# LED_ring.net
KiCad netlist of a schematic drawn in Altium Designer
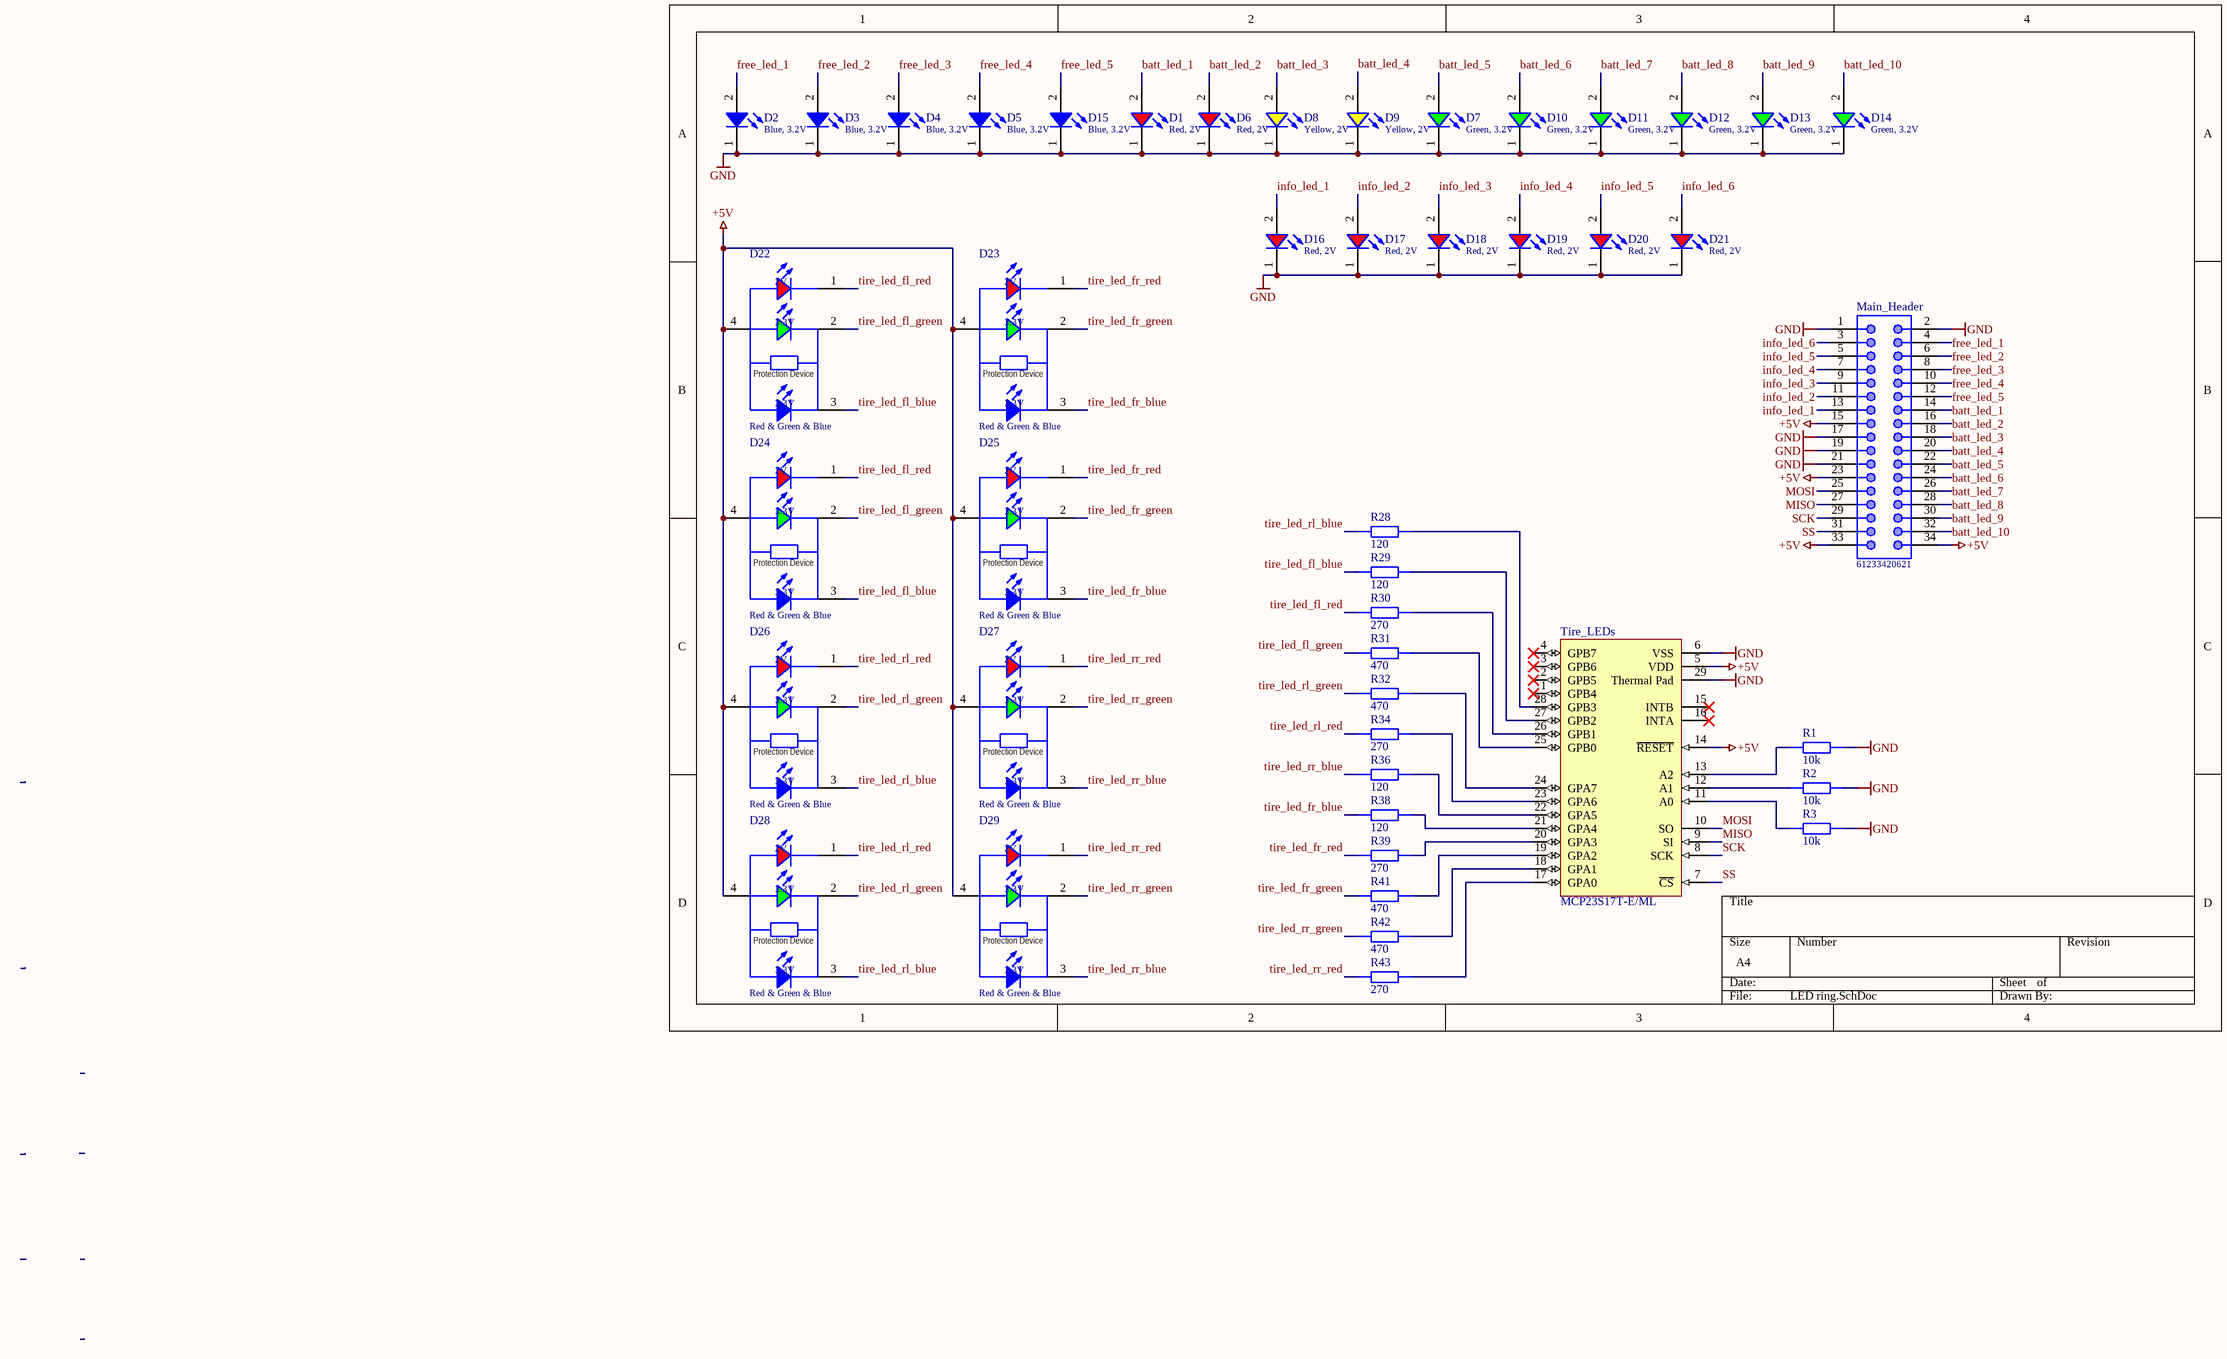
[diagram p0: LED ring.SchDoc]

(export (version "E")
  (design (tool "Eeschema 10.0.6"))
  (components
    (comp (ref "D1")
      (value "Red, 2V")
      (footprint "WL-SMCW_0805")
      (description "WL-SMCW SMT Mono-color Chip LED Waterclear, size 0805, Red, 2V, 140deg")
      (fields (field (name "PART NUMBER") "150080RS75000") (field (name "PUBLISHER") "Wurth Elektronik"))
      (libsource (lib "Altium_WL-SMCW (rev20a)") (part "150080RS75000"))
    )
    (comp (ref "D2")
      (value "Blue, 3.2V")
      (footprint "WL-SMCW_0805")
      (description "WL-SMCW SMT Mono-color Chip LED Waterclear, size 0805, Blue, 3.2V, 140deg")
      (fields (field (name "PART NUMBER") "150080BS75000") (field (name "PUBLISHER") "Wurth Elektronik"))
      (libsource (lib "Altium_WL-SMCW (rev20a)") (part "150080BS75000"))
    )
    (comp (ref "D3")
      (value "Blue, 3.2V")
      (footprint "WL-SMCW_0805")
      (description "WL-SMCW SMT Mono-color Chip LED Waterclear, size 0805, Blue, 3.2V, 140deg")
      (fields (field (name "PART NUMBER") "150080BS75000") (field (name "PUBLISHER") "Wurth Elektronik"))
      (libsource (lib "Altium_WL-SMCW (rev20a)") (part "150080BS75000"))
    )
    (comp (ref "D4")
      (value "Blue, 3.2V")
      (footprint "WL-SMCW_0805")
      (description "WL-SMCW SMT Mono-color Chip LED Waterclear, size 0805, Blue, 3.2V, 140deg")
      (fields (field (name "PART NUMBER") "150080BS75000") (field (name "PUBLISHER") "Wurth Elektronik"))
      (libsource (lib "Altium_WL-SMCW (rev20a)") (part "150080BS75000"))
    )
    (comp (ref "D5")
      (value "Blue, 3.2V")
      (footprint "WL-SMCW_0805")
      (description "WL-SMCW SMT Mono-color Chip LED Waterclear, size 0805, Blue, 3.2V, 140deg")
      (fields (field (name "PART NUMBER") "150080BS75000") (field (name "PUBLISHER") "Wurth Elektronik"))
      (libsource (lib "Altium_WL-SMCW (rev20a)") (part "150080BS75000"))
    )
    (comp (ref "D6")
      (value "Red, 2V")
      (footprint "WL-SMCW_0805")
      (description "WL-SMCW SMT Mono-color Chip LED Waterclear, size 0805, Red, 2V, 140deg")
      (fields (field (name "PART NUMBER") "150080RS75000") (field (name "PUBLISHER") "Wurth Elektronik"))
      (libsource (lib "Altium_WL-SMCW (rev20a)") (part "150080RS75000"))
    )
    (comp (ref "D7")
      (value "Green, 3.2V")
      (footprint "WL-SMCW_0805")
      (description "WL-SMCW SMT Mono-color Chip LED Waterclear, size 0805, Green, 3.2V, 140deg")
      (fields (field (name "PART NUMBER") "150080GS75000") (field (name "PUBLISHER") "Wurth Elektronik"))
      (libsource (lib "Altium_WL-SMCW (rev20a)") (part "150080GS75000"))
    )
    (comp (ref "D8")
      (value "Yellow, 2V")
      (footprint "WL-SMCW_0805")
      (description "WL-SMCW SMT Mono-color Chip LED Waterclear, size 0805, Yellow, 2V, 140deg")
      (fields (field (name "PART NUMBER") "150080YS75000") (field (name "PUBLISHER") "Wurth Elektronik"))
      (libsource (lib "Altium_WL-SMCW (rev20a)") (part "150080YS75000"))
    )
    (comp (ref "D9")
      (value "Yellow, 2V")
      (footprint "WL-SMCW_0805")
      (description "WL-SMCW SMT Mono-color Chip LED Waterclear, size 0805, Yellow, 2V, 140deg")
      (fields (field (name "PART NUMBER") "150080YS75000") (field (name "PUBLISHER") "Wurth Elektronik"))
      (libsource (lib "Altium_WL-SMCW (rev20a)") (part "150080YS75000"))
    )
    (comp (ref "D10")
      (value "Green, 3.2V")
      (footprint "WL-SMCW_0805")
      (description "WL-SMCW SMT Mono-color Chip LED Waterclear, size 0805, Green, 3.2V, 140deg")
      (fields (field (name "PART NUMBER") "150080GS75000") (field (name "PUBLISHER") "Wurth Elektronik"))
      (libsource (lib "Altium_WL-SMCW (rev20a)") (part "150080GS75000"))
    )
    (comp (ref "D11")
      (value "Green, 3.2V")
      (footprint "WL-SMCW_0805")
      (description "WL-SMCW SMT Mono-color Chip LED Waterclear, size 0805, Green, 3.2V, 140deg")
      (fields (field (name "PART NUMBER") "150080GS75000") (field (name "PUBLISHER") "Wurth Elektronik"))
      (libsource (lib "Altium_WL-SMCW (rev20a)") (part "150080GS75000"))
    )
    (comp (ref "D12")
      (value "Green, 3.2V")
      (footprint "WL-SMCW_0805")
      (description "WL-SMCW SMT Mono-color Chip LED Waterclear, size 0805, Green, 3.2V, 140deg")
      (fields (field (name "PART NUMBER") "150080GS75000") (field (name "PUBLISHER") "Wurth Elektronik"))
      (libsource (lib "Altium_WL-SMCW (rev20a)") (part "150080GS75000"))
    )
    (comp (ref "D13")
      (value "Green, 3.2V")
      (footprint "WL-SMCW_0805")
      (description "WL-SMCW SMT Mono-color Chip LED Waterclear, size 0805, Green, 3.2V, 140deg")
      (fields (field (name "PART NUMBER") "150080GS75000") (field (name "PUBLISHER") "Wurth Elektronik"))
      (libsource (lib "Altium_WL-SMCW (rev20a)") (part "150080GS75000"))
    )
    (comp (ref "D14")
      (value "Green, 3.2V")
      (footprint "WL-SMCW_0805")
      (description "WL-SMCW SMT Mono-color Chip LED Waterclear, size 0805, Green, 3.2V, 140deg")
      (fields (field (name "PART NUMBER") "150080GS75000") (field (name "PUBLISHER") "Wurth Elektronik"))
      (libsource (lib "Altium_WL-SMCW (rev20a)") (part "150080GS75000"))
    )
    (comp (ref "D15")
      (value "Blue, 3.2V")
      (footprint "WL-SMCW_0805")
      (description "WL-SMCW SMT Mono-color Chip LED Waterclear, size 0805, Blue, 3.2V, 140deg")
      (fields (field (name "PART NUMBER") "150080BS75000") (field (name "PUBLISHER") "Wurth Elektronik"))
      (libsource (lib "Altium_WL-SMCW (rev20a)") (part "150080BS75000"))
    )
    (comp (ref "D16")
      (value "Red, 2V")
      (footprint "WL-SMCW_0805")
      (description "WL-SMCW SMT Mono-color Chip LED Waterclear, size 0805, Red, 2V, 140deg")
      (fields (field (name "PART NUMBER") "150080RS75000") (field (name "PUBLISHER") "Wurth Elektronik"))
      (libsource (lib "Altium_WL-SMCW (rev20a)") (part "150080RS75000"))
    )
    (comp (ref "D17")
      (value "Red, 2V")
      (footprint "WL-SMCW_0805")
      (description "WL-SMCW SMT Mono-color Chip LED Waterclear, size 0805, Red, 2V, 140deg")
      (fields (field (name "PART NUMBER") "150080RS75000") (field (name "PUBLISHER") "Wurth Elektronik"))
      (libsource (lib "Altium_WL-SMCW (rev20a)") (part "150080RS75000"))
    )
    (comp (ref "D18")
      (value "Red, 2V")
      (footprint "WL-SMCW_0805")
      (description "WL-SMCW SMT Mono-color Chip LED Waterclear, size 0805, Red, 2V, 140deg")
      (fields (field (name "PART NUMBER") "150080RS75000") (field (name "PUBLISHER") "Wurth Elektronik"))
      (libsource (lib "Altium_WL-SMCW (rev20a)") (part "150080RS75000"))
    )
    (comp (ref "D19")
      (value "Red, 2V")
      (footprint "WL-SMCW_0805")
      (description "WL-SMCW SMT Mono-color Chip LED Waterclear, size 0805, Red, 2V, 140deg")
      (fields (field (name "PART NUMBER") "150080RS75000") (field (name "PUBLISHER") "Wurth Elektronik"))
      (libsource (lib "Altium_WL-SMCW (rev20a)") (part "150080RS75000"))
    )
    (comp (ref "D20")
      (value "Red, 2V")
      (footprint "WL-SMCW_0805")
      (description "WL-SMCW SMT Mono-color Chip LED Waterclear, size 0805, Red, 2V, 140deg")
      (fields (field (name "PART NUMBER") "150080RS75000") (field (name "PUBLISHER") "Wurth Elektronik"))
      (libsource (lib "Altium_WL-SMCW (rev20a)") (part "150080RS75000"))
    )
    (comp (ref "D21")
      (value "Red, 2V")
      (footprint "WL-SMCW_0805")
      (description "WL-SMCW SMT Mono-color Chip LED Waterclear, size 0805, Red, 2V, 140deg")
      (fields (field (name "PART NUMBER") "150080RS75000") (field (name "PUBLISHER") "Wurth Elektronik"))
      (libsource (lib "Altium_WL-SMCW (rev20a)") (part "150080RS75000"))
    )
    (comp (ref "D22")
      (value "Red & Green & Blue")
      (footprint "WL-SFCW_0805")
      (description "WL-SFCW SMT Full-color Chip LED Waterclear, size 0805, Red & Green & Blue, 120deg")
      (fields (field (name "PART NUMBER") "150080M173000") (field (name "PUBLISHER") "Wurth Elektronik"))
      (libsource (lib "Altium_WL-SFCW (rev19b)") (part "150080M173000"))
    )
    (comp (ref "D23")
      (value "Red & Green & Blue")
      (footprint "WL-SFCW_0805")
      (description "WL-SFCW SMT Full-color Chip LED Waterclear, size 0805, Red & Green & Blue, 120deg")
      (fields (field (name "PART NUMBER") "150080M173000") (field (name "PUBLISHER") "Wurth Elektronik"))
      (libsource (lib "Altium_WL-SFCW (rev19b)") (part "150080M173000"))
    )
    (comp (ref "D24")
      (value "Red & Green & Blue")
      (footprint "WL-SFCW_0805")
      (description "WL-SFCW SMT Full-color Chip LED Waterclear, size 0805, Red & Green & Blue, 120deg")
      (fields (field (name "PART NUMBER") "150080M173000") (field (name "PUBLISHER") "Wurth Elektronik"))
      (libsource (lib "Altium_WL-SFCW (rev19b)") (part "150080M173000"))
    )
    (comp (ref "D25")
      (value "Red & Green & Blue")
      (footprint "WL-SFCW_0805")
      (description "WL-SFCW SMT Full-color Chip LED Waterclear, size 0805, Red & Green & Blue, 120deg")
      (fields (field (name "PART NUMBER") "150080M173000") (field (name "PUBLISHER") "Wurth Elektronik"))
      (libsource (lib "Altium_WL-SFCW (rev19b)") (part "150080M173000"))
    )
    (comp (ref "D26")
      (value "Red & Green & Blue")
      (footprint "WL-SFCW_0805")
      (description "WL-SFCW SMT Full-color Chip LED Waterclear, size 0805, Red & Green & Blue, 120deg")
      (fields (field (name "PART NUMBER") "150080M173000") (field (name "PUBLISHER") "Wurth Elektronik"))
      (libsource (lib "Altium_WL-SFCW (rev19b)") (part "150080M173000"))
    )
    (comp (ref "D27")
      (value "Red & Green & Blue")
      (footprint "WL-SFCW_0805")
      (description "WL-SFCW SMT Full-color Chip LED Waterclear, size 0805, Red & Green & Blue, 120deg")
      (fields (field (name "PART NUMBER") "150080M173000") (field (name "PUBLISHER") "Wurth Elektronik"))
      (libsource (lib "Altium_WL-SFCW (rev19b)") (part "150080M173000"))
    )
    (comp (ref "D28")
      (value "Red & Green & Blue")
      (footprint "WL-SFCW_0805")
      (description "WL-SFCW SMT Full-color Chip LED Waterclear, size 0805, Red & Green & Blue, 120deg")
      (fields (field (name "PART NUMBER") "150080M173000") (field (name "PUBLISHER") "Wurth Elektronik"))
      (libsource (lib "Altium_WL-SFCW (rev19b)") (part "150080M173000"))
    )
    (comp (ref "D29")
      (value "Red & Green & Blue")
      (footprint "WL-SFCW_0805")
      (description "WL-SFCW SMT Full-color Chip LED Waterclear, size 0805, Red & Green & Blue, 120deg")
      (fields (field (name "PART NUMBER") "150080M173000") (field (name "PUBLISHER") "Wurth Elektronik"))
      (libsource (lib "Altium_WL-SFCW (rev19b)") (part "150080M173000"))
    )
    (comp (ref "Main_Header")
      (value "61233420621")
      (footprint "61233420621")
      (description "WR-BHD Box Header, Male PCB side, pitch 2.54mm, SMT, Straight, 34p")
      (fields (field (name "MANUFACTURER") "Wurth Elektronik"))
      (libsource (lib "Altium_WR-BHD (rev21a)") (part "61233420621"))
    )
    (comp (ref "R1")
      (value "10k")
      (footprint "STACKPOLE CSR0603")
      (description "Resistor with multiple footprints")
      (fields (field (name "Comment") "SMD Resistor"))
      (libsource (lib "Standardbauteile") (part "SMD Resistor"))
    )
    (comp (ref "R2")
      (value "10k")
      (footprint "STACKPOLE CSR0603")
      (description "Resistor with multiple footprints")
      (fields (field (name "Comment") "SMD Resistor"))
      (libsource (lib "Standardbauteile") (part "SMD Resistor"))
    )
    (comp (ref "R3")
      (value "10k")
      (footprint "STACKPOLE CSR0603")
      (description "Resistor with multiple footprints")
      (fields (field (name "Comment") "SMD Resistor"))
      (libsource (lib "Standardbauteile") (part "SMD Resistor"))
    )
    (comp (ref "R28")
      (value "120")
      (footprint "STACKPOLE CSR0603")
      (description "Resistor with multiple footprints")
      (fields (field (name "Comment") "SMD Resistor"))
      (libsource (lib "Standardbauteile") (part "SMD Resistor"))
    )
    (comp (ref "R29")
      (value "120")
      (footprint "STACKPOLE CSR0603")
      (description "Resistor with multiple footprints")
      (fields (field (name "Comment") "SMD Resistor"))
      (libsource (lib "Standardbauteile") (part "SMD Resistor"))
    )
    (comp (ref "R30")
      (value "270")
      (footprint "STACKPOLE CSR0603")
      (description "Resistor with multiple footprints")
      (fields (field (name "Comment") "SMD Resistor"))
      (libsource (lib "Standardbauteile") (part "SMD Resistor"))
    )
    (comp (ref "R31")
      (value "470")
      (footprint "STACKPOLE CSR0603")
      (description "Resistor with multiple footprints")
      (fields (field (name "Comment") "SMD Resistor"))
      (libsource (lib "Standardbauteile") (part "SMD Resistor"))
    )
    (comp (ref "R32")
      (value "470")
      (footprint "STACKPOLE CSR0603")
      (description "Resistor with multiple footprints")
      (fields (field (name "Comment") "SMD Resistor"))
      (libsource (lib "Standardbauteile") (part "SMD Resistor"))
    )
    (comp (ref "R34")
      (value "270")
      (footprint "STACKPOLE CSR0603")
      (description "Resistor with multiple footprints")
      (fields (field (name "Comment") "SMD Resistor"))
      (libsource (lib "Standardbauteile") (part "SMD Resistor"))
    )
    (comp (ref "R36")
      (value "120")
      (footprint "STACKPOLE CSR0603")
      (description "Resistor with multiple footprints")
      (fields (field (name "Comment") "SMD Resistor"))
      (libsource (lib "Standardbauteile") (part "SMD Resistor"))
    )
    (comp (ref "R38")
      (value "120")
      (footprint "STACKPOLE CSR0603")
      (description "Resistor with multiple footprints")
      (fields (field (name "Comment") "SMD Resistor"))
      (libsource (lib "Standardbauteile") (part "SMD Resistor"))
    )
    (comp (ref "R39")
      (value "270")
      (footprint "STACKPOLE CSR0603")
      (description "Resistor with multiple footprints")
      (fields (field (name "Comment") "SMD Resistor"))
      (libsource (lib "Standardbauteile") (part "SMD Resistor"))
    )
    (comp (ref "R41")
      (value "470")
      (footprint "STACKPOLE CSR0603")
      (description "Resistor with multiple footprints")
      (fields (field (name "Comment") "SMD Resistor"))
      (libsource (lib "Standardbauteile") (part "SMD Resistor"))
    )
    (comp (ref "R42")
      (value "470")
      (footprint "STACKPOLE CSR0603")
      (description "Resistor with multiple footprints")
      (fields (field (name "Comment") "SMD Resistor"))
      (libsource (lib "Standardbauteile") (part "SMD Resistor"))
    )
    (comp (ref "R43")
      (value "270")
      (footprint "STACKPOLE CSR0603")
      (description "Resistor with multiple footprints")
      (fields (field (name "Comment") "SMD Resistor"))
      (libsource (lib "Standardbauteile") (part "SMD Resistor"))
    )
    (comp (ref "Tire_LEDs")
      (value "MCP23S17T-E/ML")
      (footprint "QFN-ML28_M")
      (description "16-Bit I/O Expander with Serial Interface, 28-Pin QFN, Extended Temperature, Tape and Reel")
      (libsource (lib "Altium Content Vault") (part "PR-BUSIC-MCP23S17-29"))
    )
  )
  (nets
    (net (code "1") (name "+5V") (class "Default")
      (node (ref "D22") (pin "4") (pinfunction "A_4") (pintype "passive"))
      (node (ref "D23") (pin "4") (pinfunction "A_4") (pintype "passive"))
      (node (ref "D24") (pin "4") (pinfunction "A_4") (pintype "passive"))
      (node (ref "D25") (pin "4") (pinfunction "A_4") (pintype "passive"))
      (node (ref "D26") (pin "4") (pinfunction "A_4") (pintype "passive"))
      (node (ref "D27") (pin "4") (pinfunction "A_4") (pintype "passive"))
      (node (ref "D28") (pin "4") (pinfunction "A_4") (pintype "passive"))
      (node (ref "D29") (pin "4") (pinfunction "A_4") (pintype "passive"))
      (node (ref "Main_Header") (pin "15") (pinfunction "15_15") (pintype "passive"))
      (node (ref "Main_Header") (pin "23") (pinfunction "23_23") (pintype "passive"))
      (node (ref "Main_Header") (pin "33") (pinfunction "33_33") (pintype "passive"))
      (node (ref "Main_Header") (pin "34") (pinfunction "34_34") (pintype "passive"))
      (node (ref "Tire_LEDs") (pin "14") (pinfunction "~{RESET}_14") (pintype "input"))
      (node (ref "Tire_LEDs") (pin "5") (pinfunction "VDD_5") (pintype "power_in"))
    )
    (net (code "2") (name "/MISO") (class "Default")
      (node (ref "Main_Header") (pin "27") (pinfunction "27_27") (pintype "passive"))
      (node (ref "Tire_LEDs") (pin "9") (pinfunction "SI_9") (pintype "input"))
    )
    (net (code "3") (name "/MOSI") (class "Default")
      (node (ref "Main_Header") (pin "25") (pinfunction "25_25") (pintype "passive"))
      (node (ref "Tire_LEDs") (pin "10") (pinfunction "SO_10") (pintype "tri_state"))
    )
    (net (code "4") (name "/SCK") (class "Default")
      (node (ref "Main_Header") (pin "29") (pinfunction "29_29") (pintype "passive"))
      (node (ref "Tire_LEDs") (pin "8") (pinfunction "SCK_8") (pintype "input"))
    )
    (net (code "5") (name "/SS") (class "Default")
      (node (ref "Main_Header") (pin "31") (pinfunction "31_31") (pintype "passive"))
      (node (ref "Tire_LEDs") (pin "7") (pinfunction "~{CS}_7") (pintype "input"))
    )
    (net (code "6") (name "/batt_led_1") (class "Default")
      (node (ref "D1") (pin "2") (pinfunction "A_2") (pintype "passive"))
      (node (ref "Main_Header") (pin "14") (pinfunction "14_14") (pintype "passive"))
    )
    (net (code "7") (name "/batt_led_2") (class "Default")
      (node (ref "D6") (pin "2") (pinfunction "A_2") (pintype "passive"))
      (node (ref "Main_Header") (pin "16") (pinfunction "16_16") (pintype "passive"))
    )
    (net (code "8") (name "/batt_led_3") (class "Default")
      (node (ref "D8") (pin "2") (pinfunction "A_2") (pintype "passive"))
      (node (ref "Main_Header") (pin "18") (pinfunction "18_18") (pintype "passive"))
    )
    (net (code "9") (name "/batt_led_4") (class "Default")
      (node (ref "D9") (pin "2") (pinfunction "A_2") (pintype "passive"))
      (node (ref "Main_Header") (pin "20") (pinfunction "20_20") (pintype "passive"))
    )
    (net (code "10") (name "/batt_led_5") (class "Default")
      (node (ref "D7") (pin "2") (pinfunction "A_2") (pintype "passive"))
      (node (ref "Main_Header") (pin "22") (pinfunction "22_22") (pintype "passive"))
    )
    (net (code "11") (name "/batt_led_6") (class "Default")
      (node (ref "D10") (pin "2") (pinfunction "A_2") (pintype "passive"))
      (node (ref "Main_Header") (pin "24") (pinfunction "24_24") (pintype "passive"))
    )
    (net (code "12") (name "/batt_led_7") (class "Default")
      (node (ref "D11") (pin "2") (pinfunction "A_2") (pintype "passive"))
      (node (ref "Main_Header") (pin "26") (pinfunction "26_26") (pintype "passive"))
    )
    (net (code "13") (name "/batt_led_8") (class "Default")
      (node (ref "D12") (pin "2") (pinfunction "A_2") (pintype "passive"))
      (node (ref "Main_Header") (pin "28") (pinfunction "28_28") (pintype "passive"))
    )
    (net (code "14") (name "/batt_led_9") (class "Default")
      (node (ref "D13") (pin "2") (pinfunction "A_2") (pintype "passive"))
      (node (ref "Main_Header") (pin "30") (pinfunction "30_30") (pintype "passive"))
    )
    (net (code "15") (name "/batt_led_10") (class "Default")
      (node (ref "D14") (pin "2") (pinfunction "A_2") (pintype "passive"))
      (node (ref "Main_Header") (pin "32") (pinfunction "32_32") (pintype "passive"))
    )
    (net (code "16") (name "/free_led_1") (class "Default")
      (node (ref "D2") (pin "2") (pinfunction "A_2") (pintype "passive"))
      (node (ref "Main_Header") (pin "4") (pinfunction "4_4") (pintype "passive"))
    )
    (net (code "17") (name "/free_led_2") (class "Default")
      (node (ref "D3") (pin "2") (pinfunction "A_2") (pintype "passive"))
      (node (ref "Main_Header") (pin "6") (pinfunction "6_6") (pintype "passive"))
    )
    (net (code "18") (name "/free_led_3") (class "Default")
      (node (ref "D4") (pin "2") (pinfunction "A_2") (pintype "passive"))
      (node (ref "Main_Header") (pin "8") (pinfunction "8_8") (pintype "passive"))
    )
    (net (code "19") (name "/free_led_4") (class "Default")
      (node (ref "D5") (pin "2") (pinfunction "A_2") (pintype "passive"))
      (node (ref "Main_Header") (pin "10") (pinfunction "10_10") (pintype "passive"))
    )
    (net (code "20") (name "/free_led_5") (class "Default")
      (node (ref "D15") (pin "2") (pinfunction "A_2") (pintype "passive"))
      (node (ref "Main_Header") (pin "12") (pinfunction "12_12") (pintype "passive"))
    )
    (net (code "21") (name "/info_led_1") (class "Default")
      (node (ref "D16") (pin "2") (pinfunction "A_2") (pintype "passive"))
      (node (ref "Main_Header") (pin "13") (pinfunction "13_13") (pintype "passive"))
    )
    (net (code "22") (name "/info_led_2") (class "Default")
      (node (ref "D17") (pin "2") (pinfunction "A_2") (pintype "passive"))
      (node (ref "Main_Header") (pin "11") (pinfunction "11_11") (pintype "passive"))
    )
    (net (code "23") (name "/info_led_3") (class "Default")
      (node (ref "D18") (pin "2") (pinfunction "A_2") (pintype "passive"))
      (node (ref "Main_Header") (pin "9") (pinfunction "9_9") (pintype "passive"))
    )
    (net (code "24") (name "/info_led_4") (class "Default")
      (node (ref "D19") (pin "2") (pinfunction "A_2") (pintype "passive"))
      (node (ref "Main_Header") (pin "7") (pinfunction "7_7") (pintype "passive"))
    )
    (net (code "25") (name "/info_led_5") (class "Default")
      (node (ref "D20") (pin "2") (pinfunction "A_2") (pintype "passive"))
      (node (ref "Main_Header") (pin "5") (pinfunction "5_5") (pintype "passive"))
    )
    (net (code "26") (name "/info_led_6") (class "Default")
      (node (ref "D21") (pin "2") (pinfunction "A_2") (pintype "passive"))
      (node (ref "Main_Header") (pin "3") (pinfunction "3_3") (pintype "passive"))
    )
    (net (code "27") (name "/tire_led_fl_blue") (class "Default")
      (node (ref "D22") (pin "3") (pinfunction "K_3") (pintype "passive"))
      (node (ref "D24") (pin "3") (pinfunction "K_3") (pintype "passive"))
      (node (ref "R29") (pin "2") (pinfunction "2_2") (pintype "passive"))
    )
    (net (code "28") (name "/tire_led_fl_green") (class "Default")
      (node (ref "D22") (pin "2") (pinfunction "K_2") (pintype "passive"))
      (node (ref "D24") (pin "2") (pinfunction "K_2") (pintype "passive"))
      (node (ref "R31") (pin "2") (pinfunction "2_2") (pintype "passive"))
    )
    (net (code "29") (name "/tire_led_fl_red") (class "Default")
      (node (ref "D22") (pin "1") (pinfunction "K_1") (pintype "passive"))
      (node (ref "D24") (pin "1") (pinfunction "K_1") (pintype "passive"))
      (node (ref "R30") (pin "2") (pinfunction "2_2") (pintype "passive"))
    )
    (net (code "30") (name "/tire_led_fr_blue") (class "Default")
      (node (ref "D23") (pin "3") (pinfunction "K_3") (pintype "passive"))
      (node (ref "D25") (pin "3") (pinfunction "K_3") (pintype "passive"))
      (node (ref "R38") (pin "2") (pinfunction "2_2") (pintype "passive"))
    )
    (net (code "31") (name "/tire_led_fr_green") (class "Default")
      (node (ref "D23") (pin "2") (pinfunction "K_2") (pintype "passive"))
      (node (ref "D25") (pin "2") (pinfunction "K_2") (pintype "passive"))
      (node (ref "R41") (pin "2") (pinfunction "2_2") (pintype "passive"))
    )
    (net (code "32") (name "/tire_led_fr_red") (class "Default")
      (node (ref "D23") (pin "1") (pinfunction "K_1") (pintype "passive"))
      (node (ref "D25") (pin "1") (pinfunction "K_1") (pintype "passive"))
      (node (ref "R39") (pin "2") (pinfunction "2_2") (pintype "passive"))
    )
    (net (code "33") (name "/tire_led_rl_blue") (class "Default")
      (node (ref "D26") (pin "3") (pinfunction "K_3") (pintype "passive"))
      (node (ref "D28") (pin "3") (pinfunction "K_3") (pintype "passive"))
      (node (ref "R28") (pin "2") (pinfunction "2_2") (pintype "passive"))
    )
    (net (code "34") (name "/tire_led_rl_green") (class "Default")
      (node (ref "D26") (pin "2") (pinfunction "K_2") (pintype "passive"))
      (node (ref "D28") (pin "2") (pinfunction "K_2") (pintype "passive"))
      (node (ref "R32") (pin "2") (pinfunction "2_2") (pintype "passive"))
    )
    (net (code "35") (name "/tire_led_rl_red") (class "Default")
      (node (ref "D26") (pin "1") (pinfunction "K_1") (pintype "passive"))
      (node (ref "D28") (pin "1") (pinfunction "K_1") (pintype "passive"))
      (node (ref "R34") (pin "2") (pinfunction "2_2") (pintype "passive"))
    )
    (net (code "36") (name "/tire_led_rr_blue") (class "Default")
      (node (ref "D27") (pin "3") (pinfunction "K_3") (pintype "passive"))
      (node (ref "D29") (pin "3") (pinfunction "K_3") (pintype "passive"))
      (node (ref "R36") (pin "2") (pinfunction "2_2") (pintype "passive"))
    )
    (net (code "37") (name "/tire_led_rr_green") (class "Default")
      (node (ref "D27") (pin "2") (pinfunction "K_2") (pintype "passive"))
      (node (ref "D29") (pin "2") (pinfunction "K_2") (pintype "passive"))
      (node (ref "R42") (pin "2") (pinfunction "2_2") (pintype "passive"))
    )
    (net (code "38") (name "/tire_led_rr_red") (class "Default")
      (node (ref "D27") (pin "1") (pinfunction "K_1") (pintype "passive"))
      (node (ref "D29") (pin "1") (pinfunction "K_1") (pintype "passive"))
      (node (ref "R43") (pin "2") (pinfunction "2_2") (pintype "passive"))
    )
    (net (code "39") (name "GND") (class "Default")
      (node (ref "D1") (pin "1") (pinfunction "K_1") (pintype "passive"))
      (node (ref "D10") (pin "1") (pinfunction "K_1") (pintype "passive"))
      (node (ref "D11") (pin "1") (pinfunction "K_1") (pintype "passive"))
      (node (ref "D12") (pin "1") (pinfunction "K_1") (pintype "passive"))
      (node (ref "D13") (pin "1") (pinfunction "K_1") (pintype "passive"))
      (node (ref "D14") (pin "1") (pinfunction "K_1") (pintype "passive"))
      (node (ref "D15") (pin "1") (pinfunction "K_1") (pintype "passive"))
      (node (ref "D16") (pin "1") (pinfunction "K_1") (pintype "passive"))
      (node (ref "D17") (pin "1") (pinfunction "K_1") (pintype "passive"))
      (node (ref "D18") (pin "1") (pinfunction "K_1") (pintype "passive"))
      (node (ref "D19") (pin "1") (pinfunction "K_1") (pintype "passive"))
      (node (ref "D2") (pin "1") (pinfunction "K_1") (pintype "passive"))
      (node (ref "D20") (pin "1") (pinfunction "K_1") (pintype "passive"))
      (node (ref "D21") (pin "1") (pinfunction "K_1") (pintype "passive"))
      (node (ref "D3") (pin "1") (pinfunction "K_1") (pintype "passive"))
      (node (ref "D4") (pin "1") (pinfunction "K_1") (pintype "passive"))
      (node (ref "D5") (pin "1") (pinfunction "K_1") (pintype "passive"))
      (node (ref "D6") (pin "1") (pinfunction "K_1") (pintype "passive"))
      (node (ref "D7") (pin "1") (pinfunction "K_1") (pintype "passive"))
      (node (ref "D8") (pin "1") (pinfunction "K_1") (pintype "passive"))
      (node (ref "D9") (pin "1") (pinfunction "K_1") (pintype "passive"))
      (node (ref "Main_Header") (pin "1") (pinfunction "1_1") (pintype "passive"))
      (node (ref "Main_Header") (pin "17") (pinfunction "17_17") (pintype "passive"))
      (node (ref "Main_Header") (pin "19") (pinfunction "19_19") (pintype "passive"))
      (node (ref "Main_Header") (pin "2") (pinfunction "2_2") (pintype "passive"))
      (node (ref "Main_Header") (pin "21") (pinfunction "21_21") (pintype "passive"))
      (node (ref "R1") (pin "2") (pinfunction "2_2") (pintype "passive"))
      (node (ref "R2") (pin "2") (pinfunction "2_2") (pintype "passive"))
      (node (ref "R3") (pin "2") (pinfunction "2_2") (pintype "passive"))
      (node (ref "Tire_LEDs") (pin "29") (pinfunction "Thermal_Pad_29") (pintype "passive"))
      (node (ref "Tire_LEDs") (pin "6") (pinfunction "VSS_6") (pintype "power_in"))
    )
    (net (code "40") (name "Net-(Tire_LEDs-A0)") (class "Default")
      (node (ref "R3") (pin "1") (pinfunction "1_1") (pintype "passive"))
      (node (ref "Tire_LEDs") (pin "11") (pinfunction "A0_11") (pintype "input"))
    )
    (net (code "41") (name "Net-(Tire_LEDs-A1)") (class "Default")
      (node (ref "R2") (pin "1") (pinfunction "1_1") (pintype "passive"))
      (node (ref "Tire_LEDs") (pin "12") (pinfunction "A1_12") (pintype "input"))
    )
    (net (code "42") (name "Net-(Tire_LEDs-A2)") (class "Default")
      (node (ref "R1") (pin "1") (pinfunction "1_1") (pintype "passive"))
      (node (ref "Tire_LEDs") (pin "13") (pinfunction "A2_13") (pintype "input"))
    )
    (net (code "43") (name "Net-(Tire_LEDs-GPA0)") (class "Default")
      (node (ref "R43") (pin "1") (pinfunction "1_1") (pintype "passive"))
      (node (ref "Tire_LEDs") (pin "17") (pinfunction "GPA0_17") (pintype "bidirectional"))
    )
    (net (code "44") (name "Net-(Tire_LEDs-GPA1)") (class "Default")
      (node (ref "R42") (pin "1") (pinfunction "1_1") (pintype "passive"))
      (node (ref "Tire_LEDs") (pin "18") (pinfunction "GPA1_18") (pintype "bidirectional"))
    )
    (net (code "45") (name "Net-(Tire_LEDs-GPA2)") (class "Default")
      (node (ref "R41") (pin "1") (pinfunction "1_1") (pintype "passive"))
      (node (ref "Tire_LEDs") (pin "19") (pinfunction "GPA2_19") (pintype "bidirectional"))
    )
    (net (code "46") (name "Net-(Tire_LEDs-GPA3)") (class "Default")
      (node (ref "R39") (pin "1") (pinfunction "1_1") (pintype "passive"))
      (node (ref "Tire_LEDs") (pin "20") (pinfunction "GPA3_20") (pintype "bidirectional"))
    )
    (net (code "47") (name "Net-(Tire_LEDs-GPA4)") (class "Default")
      (node (ref "R38") (pin "1") (pinfunction "1_1") (pintype "passive"))
      (node (ref "Tire_LEDs") (pin "21") (pinfunction "GPA4_21") (pintype "bidirectional"))
    )
    (net (code "48") (name "Net-(Tire_LEDs-GPA5)") (class "Default")
      (node (ref "R36") (pin "1") (pinfunction "1_1") (pintype "passive"))
      (node (ref "Tire_LEDs") (pin "22") (pinfunction "GPA5_22") (pintype "bidirectional"))
    )
    (net (code "49") (name "Net-(Tire_LEDs-GPA6)") (class "Default")
      (node (ref "R34") (pin "1") (pinfunction "1_1") (pintype "passive"))
      (node (ref "Tire_LEDs") (pin "23") (pinfunction "GPA6_23") (pintype "bidirectional"))
    )
    (net (code "50") (name "Net-(Tire_LEDs-GPA7)") (class "Default")
      (node (ref "R32") (pin "1") (pinfunction "1_1") (pintype "passive"))
      (node (ref "Tire_LEDs") (pin "24") (pinfunction "GPA7_24") (pintype "bidirectional"))
    )
    (net (code "51") (name "Net-(Tire_LEDs-GPB0)") (class "Default")
      (node (ref "R31") (pin "1") (pinfunction "1_1") (pintype "passive"))
      (node (ref "Tire_LEDs") (pin "25") (pinfunction "GPB0_25") (pintype "bidirectional"))
    )
    (net (code "52") (name "Net-(Tire_LEDs-GPB1)") (class "Default")
      (node (ref "R30") (pin "1") (pinfunction "1_1") (pintype "passive"))
      (node (ref "Tire_LEDs") (pin "26") (pinfunction "GPB1_26") (pintype "bidirectional"))
    )
    (net (code "53") (name "Net-(Tire_LEDs-GPB2)") (class "Default")
      (node (ref "R29") (pin "1") (pinfunction "1_1") (pintype "passive"))
      (node (ref "Tire_LEDs") (pin "27") (pinfunction "GPB2_27") (pintype "bidirectional"))
    )
    (net (code "54") (name "Net-(Tire_LEDs-GPB3)") (class "Default")
      (node (ref "R28") (pin "1") (pinfunction "1_1") (pintype "passive"))
      (node (ref "Tire_LEDs") (pin "28") (pinfunction "GPB3_28") (pintype "bidirectional"))
    )
    (net (code "55") (name "unconnected-(Tire_LEDs-GPB4-Pad1)") (class "Default")
      (node (ref "Tire_LEDs") (pin "1") (pinfunction "GPB4_1") (pintype "bidirectional+no_connect"))
    )
    (net (code "56") (name "unconnected-(Tire_LEDs-GPB5-Pad2)") (class "Default")
      (node (ref "Tire_LEDs") (pin "2") (pinfunction "GPB5_2") (pintype "bidirectional+no_connect"))
    )
    (net (code "57") (name "unconnected-(Tire_LEDs-GPB6-Pad3)") (class "Default")
      (node (ref "Tire_LEDs") (pin "3") (pinfunction "GPB6_3") (pintype "bidirectional+no_connect"))
    )
    (net (code "58") (name "unconnected-(Tire_LEDs-GPB7-Pad4)") (class "Default")
      (node (ref "Tire_LEDs") (pin "4") (pinfunction "GPB7_4") (pintype "bidirectional+no_connect"))
    )
    (net (code "59") (name "unconnected-(Tire_LEDs-INTA-Pad16)") (class "Default")
      (node (ref "Tire_LEDs") (pin "16") (pinfunction "INTA_16") (pintype "open_collector+no_connect"))
    )
    (net (code "60") (name "unconnected-(Tire_LEDs-INTB-Pad15)") (class "Default")
      (node (ref "Tire_LEDs") (pin "15") (pinfunction "INTB_15") (pintype "open_collector+no_connect"))
    )
  )
)
